# Tail_Power_PCB.net
KiCad netlist of a schematic drawn in EAGLE
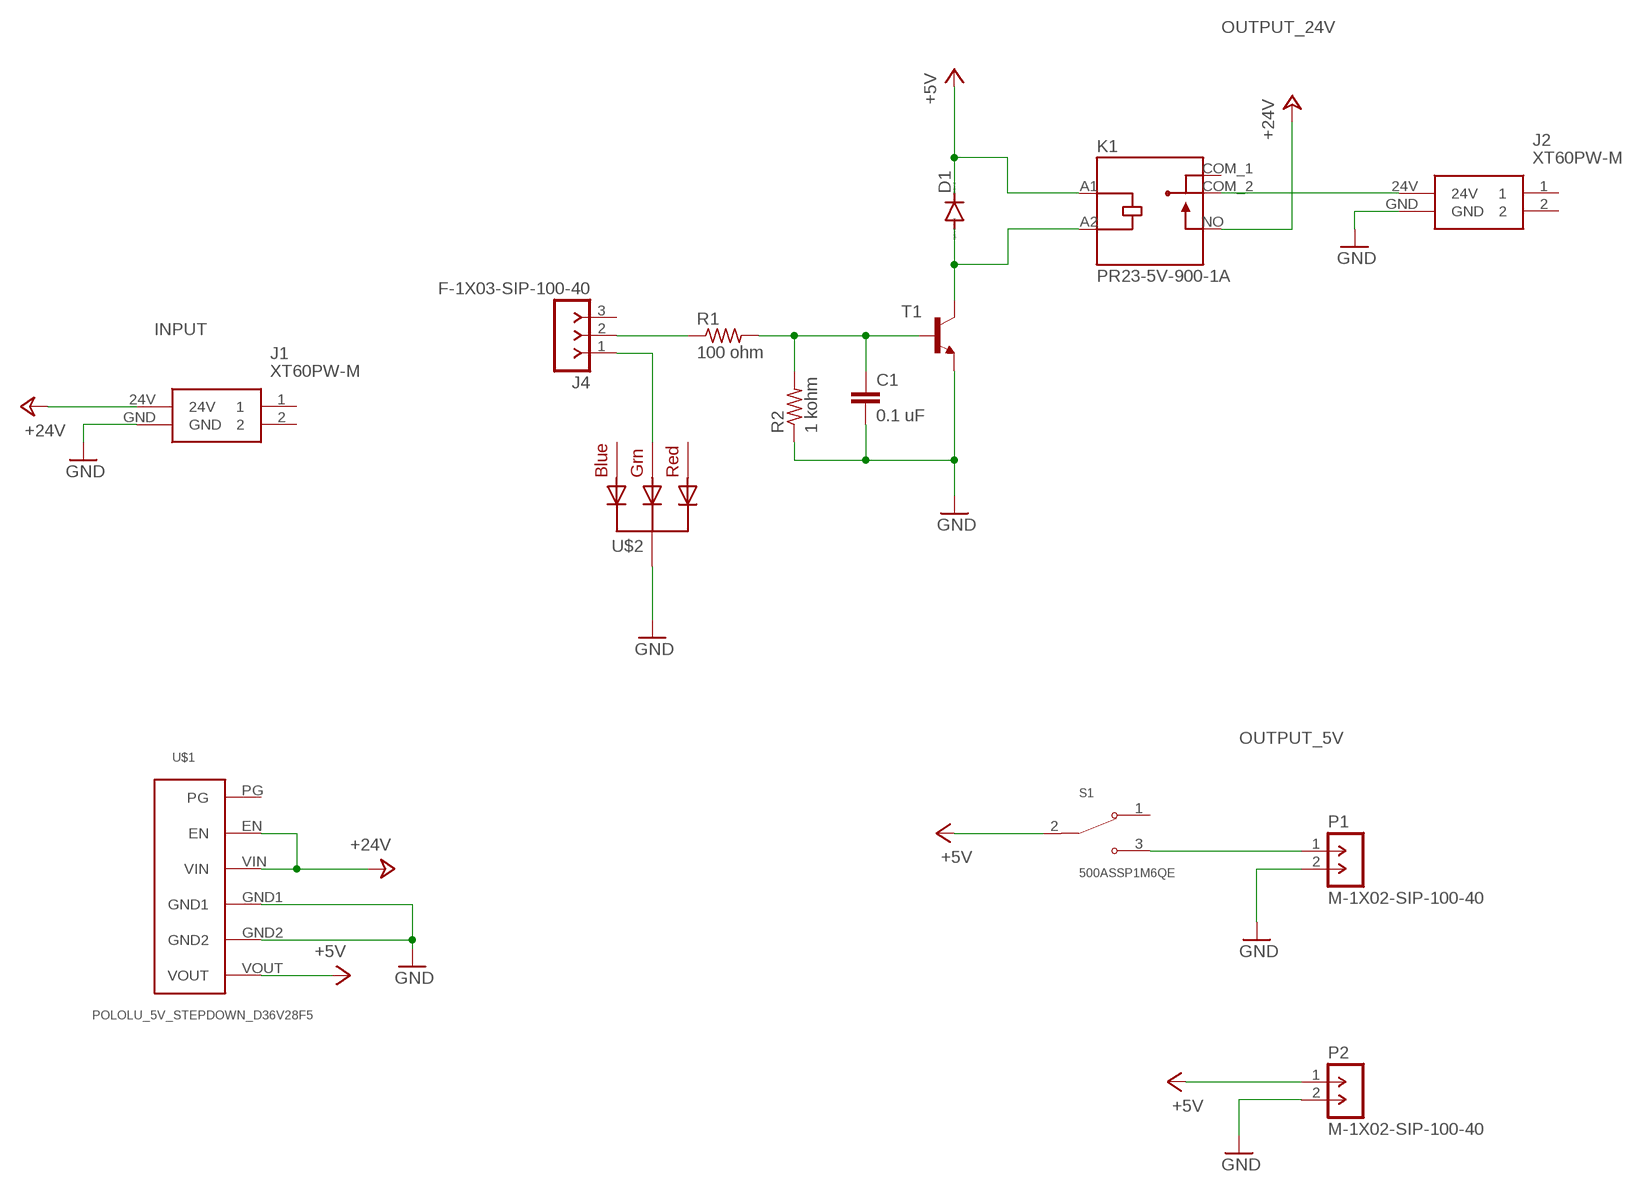
[diagram p0: schematic, sheet 1]

(export (version "E")
  (design (tool "Eeschema 10.0.6"))
  (components
    (comp (ref "C1")
      (value "0.1 uF")
      (footprint "eagle-import:C10B4")
      (libsource (lib "eagle-import") (part "C10/4"))
    )
    (comp (ref "D1")
      (value "DIODE-DO41-7.6")
      (footprint "eagle-import:DO41-7.6")
      (libsource (lib "eagle-import") (part "DIODE-DO41-7.6"))
    )
    (comp (ref "J1")
      (value "XT60PW-M")
      (footprint "eagle-import:XT60PWM")
      (libsource (lib "eagle-import") (part "XT60PW-M"))
    )
    (comp (ref "J2")
      (value "XT60PW-M")
      (footprint "eagle-import:XT60PWM")
      (libsource (lib "eagle-import") (part "XT60PW-M"))
    )
    (comp (ref "J4")
      (value "F-1X03-SIP-100-40")
      (footprint "eagle-import:SIP-100-03-40")
      (libsource (lib "eagle-import") (part "F-1X03-SIP-100-40"))
    )
    (comp (ref "K1")
      (value "PR23-5V-900-1A")
      (footprint "eagle-import:RELAY_PR23-5V-900-1A")
      (fields (field (name "MANUFACTURER") "CUI Devices"))
      (libsource (lib "eagle-import") (part "PR23-5V-900-1A"))
    )
    (comp (ref "P1")
      (value "M-1X02-SIP-100-40")
      (footprint "eagle-import:SIP-100-02-40")
      (libsource (lib "eagle-import") (part "M-1X02-SIP-100-40"))
    )
    (comp (ref "P2")
      (value "M-1X02-SIP-100-40")
      (footprint "eagle-import:SIP-100-02-40")
      (libsource (lib "eagle-import") (part "M-1X02-SIP-100-40"))
    )
    (comp (ref "R1")
      (value "100 ohm")
      (footprint "eagle-import:0204_7")
      (libsource (lib "eagle-import") (part "R-US_0204/7"))
    )
    (comp (ref "R2")
      (value "1 kohm")
      (footprint "eagle-import:0204_7")
      (libsource (lib "eagle-import") (part "R-US_0204/7"))
    )
    (comp (ref "S1")
      (value "500ASSP1M6QE")
      (footprint "eagle-import:SW_500ASSP1M6QE")
      (fields (field (name "MANUFACTURER") "E-Switch"))
      (libsource (lib "eagle-import") (part "500ASSP1M6QE"))
    )
    (comp (ref "T1")
      (value "-NPN-TO92")
      (footprint "eagle-import:TO92")
      (libsource (lib "eagle-import") (part "-NPN-TO92"))
    )
    (comp (ref "U$1")
      (value "POLOLU_5V_STEPDOWN_D36V28F5")
      (footprint "eagle-import:MODULE_POLOLU_3782")
      (libsource (lib "eagle-import") (part "POLOLU_5V_STEPDOWN_D36V28F5"))
    )
    (comp (ref "U$2")
      (value "KINGBRIGHT_LED")
      (footprint "eagle-import:LEDWP154A4SUREQBFZGW")
      (libsource (lib "eagle-import") (part "KINGBRIGHT_LED"))
    )
  )
  (nets
    (net (code "1") (name "+5V") (class "Default")
      (node (ref "D1") (pin "C") (pinfunction "C_C") (pintype "passive"))
      (node (ref "K1") (pin "A1") (pinfunction "COIL1_A1") (pintype "passive"))
      (node (ref "P2") (pin "1") (pinfunction "1_1") (pintype "passive"))
      (node (ref "S1") (pin "2") (pinfunction "COM_2") (pintype "passive"))
      (node (ref "U$1") (pin "VOUT") (pinfunction "VOUT_VOUT") (pintype "bidirectional"))
    )
    (net (code "2") (name "+24V") (class "Default")
      (node (ref "J1") (pin "24V") (pinfunction "24V_24V") (pintype "bidirectional"))
      (node (ref "K1") (pin "NO") (pinfunction "NO_NO") (pintype "passive"))
      (node (ref "U$1") (pin "EN") (pinfunction "EN_EN") (pintype "bidirectional"))
      (node (ref "U$1") (pin "VIN") (pinfunction "VIN_VIN") (pintype "bidirectional"))
    )
    (net (code "3") (name "GND") (class "Default")
      (node (ref "C1") (pin "2") (pinfunction "2_2") (pintype "passive"))
      (node (ref "J1") (pin "GND") (pinfunction "GND_GND") (pintype "bidirectional"))
      (node (ref "J2") (pin "GND") (pinfunction "GND_GND") (pintype "bidirectional"))
      (node (ref "P1") (pin "2") (pinfunction "2_2") (pintype "passive"))
      (node (ref "P2") (pin "2") (pinfunction "2_2") (pintype "passive"))
      (node (ref "R2") (pin "1") (pinfunction "1_1") (pintype "passive"))
      (node (ref "T1") (pin "1") (pinfunction "E_1") (pintype "passive"))
      (node (ref "U$1") (pin "GND1") (pinfunction "GND1_GND1") (pintype "bidirectional"))
      (node (ref "U$1") (pin "GND2") (pinfunction "GND2_GND2") (pintype "bidirectional"))
      (node (ref "U$2") (pin "GND") (pinfunction "GND_GND") (pintype "bidirectional"))
    )
    (net (code "4") (name "Net-(J4-Pad2)") (class "Default")
      (node (ref "J4") (pin "2") (pinfunction "2_2") (pintype "passive"))
      (node (ref "R1") (pin "1") (pinfunction "1_1") (pintype "passive"))
    )
    (net (code "5") (name "Net-(K1-COIL2)") (class "Default")
      (node (ref "D1") (pin "A") (pinfunction "A_A") (pintype "passive"))
      (node (ref "K1") (pin "A2") (pinfunction "COIL2_A2") (pintype "passive"))
      (node (ref "T1") (pin "3") (pinfunction "C_3") (pintype "passive"))
    )
    (net (code "6") (name "Net-(K1-COM2)") (class "Default")
      (node (ref "J2") (pin "24V") (pinfunction "24V_24V") (pintype "bidirectional"))
      (node (ref "K1") (pin "COM_2") (pinfunction "COM2_COM_2") (pintype "passive"))
    )
    (net (code "7") (name "Net-(S1-NO)") (class "Default")
      (node (ref "P1") (pin "1") (pinfunction "1_1") (pintype "passive"))
      (node (ref "S1") (pin "3") (pinfunction "NO_3") (pintype "passive"))
    )
    (net (code "8") (name "Net-(T1-B)") (class "Default")
      (node (ref "C1") (pin "1") (pinfunction "1_1") (pintype "passive"))
      (node (ref "R1") (pin "2") (pinfunction "2_2") (pintype "passive"))
      (node (ref "R2") (pin "2") (pinfunction "2_2") (pintype "passive"))
      (node (ref "T1") (pin "2") (pinfunction "B_2") (pintype "passive"))
    )
    (net (code "9") (name "Net-(U$2-GREEN)") (class "Default")
      (node (ref "J4") (pin "1") (pinfunction "1_1") (pintype "passive"))
      (node (ref "U$2") (pin "GRN") (pinfunction "GREEN_GRN") (pintype "bidirectional"))
    )
    (net (code "10") (name "unconnected-(J1-Pad1)") (class "Default")
      (node (ref "J1") (pin "1") (pinfunction "1_1") (pintype "bidirectional"))
    )
    (net (code "11") (name "unconnected-(J1-Pad2)") (class "Default")
      (node (ref "J1") (pin "2") (pinfunction "2_2") (pintype "bidirectional"))
    )
    (net (code "12") (name "unconnected-(J2-Pad1)") (class "Default")
      (node (ref "J2") (pin "1") (pinfunction "1_1") (pintype "bidirectional"))
    )
    (net (code "13") (name "unconnected-(J2-Pad2)") (class "Default")
      (node (ref "J2") (pin "2") (pinfunction "2_2") (pintype "bidirectional"))
    )
    (net (code "14") (name "unconnected-(J4-Pad3)") (class "Default")
      (node (ref "J4") (pin "3") (pinfunction "3_3") (pintype "passive"))
    )
    (net (code "15") (name "unconnected-(K1-COM1-PadCOM_1)") (class "Default")
      (node (ref "K1") (pin "COM_1") (pinfunction "COM1_COM_1") (pintype "passive"))
    )
    (net (code "16") (name "unconnected-(S1-NC-Pad1)") (class "Default")
      (node (ref "S1") (pin "1") (pinfunction "NC_1") (pintype "passive"))
    )
    (net (code "17") (name "unconnected-(U$1-PadPG)") (class "Default")
      (node (ref "U$1") (pin "PG") (pinfunction "PG_PG") (pintype "bidirectional"))
    )
    (net (code "18") (name "unconnected-(U$2-BLUE-PadBLU)") (class "Default")
      (node (ref "U$2") (pin "BLU") (pinfunction "BLUE_BLU") (pintype "bidirectional"))
    )
    (net (code "19") (name "unconnected-(U$2-PadRED)") (class "Default")
      (node (ref "U$2") (pin "RED") (pinfunction "RED_RED") (pintype "bidirectional"))
    )
  )
)
